# battery.net
KiCad netlist of a schematic drawn in Altium Designer
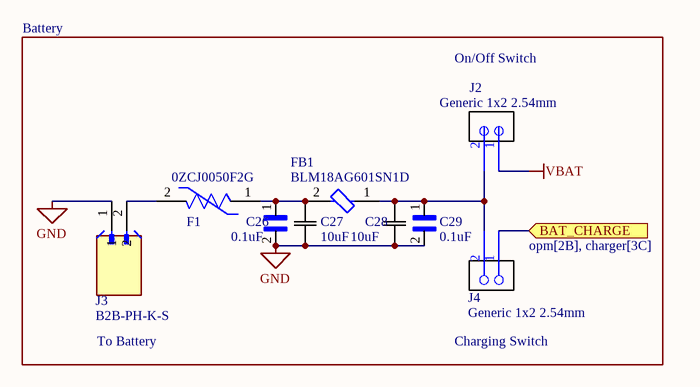
[diagram p0: battery.SchDoc]

(export (version "E")
  (design (tool "Eeschema 10.0.6"))
  (components
    (comp (ref "C26")
      (value "0.1uF")
      (footprint "CC0603JRX7R8BB104")
      (description "25V 100nF X7R ±5% 0603 Multilayer Ceramic Capacitors MLCC - SMD/SMT ROHS")
      (fields
        (field (name "MANUFACTURER") "Yageo Group")
        (field (name "MANUFACTURER PART NUMBER") "CC0603JRX7R8BB104")
      )
      (libsource (lib "opm_lib") (part "CC0603JRX7R8BB104"))
    )
    (comp (ref "C27")
      (value "10uF")
      (footprint "CC0805KKX7R7BB106")
      (description "16V 10uF X7R ±10% 0805 Multilayer Ceramic Capacitors MLCC - SMD/SMT ROHS")
      (fields
        (field (name "MANUFACTURER") "Yageo Group")
        (field (name "MANUFACTURER PART NUMBER") "CC0805KKX7R7BB106")
      )
      (libsource (lib "opm_lib") (part "CC0805KKX7R7BB106"))
    )
    (comp (ref "C28")
      (value "10uF")
      (footprint "CC0805KKX7R7BB106")
      (description "16V 10uF X7R ±10% 0805 Multilayer Ceramic Capacitors MLCC - SMD/SMT ROHS")
      (fields
        (field (name "MANUFACTURER") "Yageo Group")
        (field (name "MANUFACTURER PART NUMBER") "CC0805KKX7R7BB106")
      )
      (libsource (lib "opm_lib") (part "CC0805KKX7R7BB106"))
    )
    (comp (ref "C29")
      (value "0.1uF")
      (footprint "CC0603JRX7R8BB104")
      (description "25V 100nF X7R ±5% 0603 Multilayer Ceramic Capacitors MLCC - SMD/SMT ROHS")
      (fields
        (field (name "MANUFACTURER") "Yageo Group")
        (field (name "MANUFACTURER PART NUMBER") "CC0603JRX7R8BB104")
      )
      (libsource (lib "opm_lib") (part "CC0603JRX7R8BB104"))
    )
    (comp (ref "F1")
      (value "0ZCJ0050F2G")
      (footprint "0ZCJ0050FF2G")
      (description "Resettable Fuse, PPTC, 1206 (3216 Metric), 0ZCJ Series, 8 VDC, 500 mA, 1 A, 0.1 s")
      (fields
        (field (name "MANUFACTURER") "Bel Fuse")
        (field (name "MANUFACTURER PART NUMBER") "0ZCJ0050FF2G")
      )
      (libsource (lib "opm_lib") (part "0ZCJ0050FF2G"))
    )
    (comp (ref "FB1")
      (value "BLM18AG601SN1D")
      (footprint "BLM18AG601SN1D")
      (description "Ferrite Beads Multi-Layer 600Ohm 25% 100MHz 500mA 380mOhm DCR 0603 Automotive Paper T/R")
      (fields (field (name "MANUFACTURER") "Murata") (field (name "TOLERANCE") "25%"))
      (libsource (lib "opm_lib") (part "BLM18AG601SN1D"))
    )
    (comp (ref "J2")
      (value "Generic 1x2 2.54mm")
      (footprint "GENERIC 1X2 2.54mm")
      (libsource (lib "opm_lib") (part "Generic 1x2 2.54mm"))
    )
    (comp (ref "J3")
      (value "B2B-PH-K-S")
      (footprint "JST_B2B-PH-K-S")
      (description "CONN HEADER VERT 2POS 2MM / 2.0mm pitch/Disconnectable Crimp style connectors")
      (fields (field (name "MANUFACTURER") "JST"))
      (libsource (lib "opm_lib") (part "B2B-PH-K-S"))
    )
    (comp (ref "J4")
      (value "Generic 1x2 2.54mm")
      (footprint "GENERIC 1X2 2.54mm")
      (libsource (lib "opm_lib") (part "Generic 1x2 2.54mm"))
    )
  )
  (nets
    (net (code "1") (name "/BAT_CHARGE") (class "Default")
      (node (ref "J4") (pin "1") (pinfunction "1_1") (pintype "passive"))
    )
    (net (code "2") (name "GND") (class "Default")
      (node (ref "C26") (pin "2") (pinfunction "2_2") (pintype "passive"))
      (node (ref "C27") (pin "1") (pinfunction "1_1") (pintype "passive"))
      (node (ref "C28") (pin "1") (pinfunction "1_1") (pintype "passive"))
      (node (ref "C29") (pin "2") (pinfunction "2_2") (pintype "passive"))
      (node (ref "J3") (pin "1") (pinfunction "1_1") (pintype "passive"))
    )
    (net (code "3") (name "Net-(C26-Pad1)") (class "Default")
      (node (ref "C26") (pin "1") (pinfunction "1_1") (pintype "passive"))
      (node (ref "C27") (pin "2") (pinfunction "2_2") (pintype "passive"))
      (node (ref "F1") (pin "1") (pinfunction "1_1") (pintype "passive"))
      (node (ref "FB1") (pin "2") (pinfunction "2_2") (pintype "passive"))
    )
    (net (code "4") (name "Net-(C28-Pad2)") (class "Default")
      (node (ref "C28") (pin "2") (pinfunction "2_2") (pintype "passive"))
      (node (ref "C29") (pin "1") (pinfunction "1_1") (pintype "passive"))
      (node (ref "FB1") (pin "1") (pinfunction "1_1") (pintype "passive"))
      (node (ref "J2") (pin "2") (pinfunction "2_2") (pintype "passive"))
      (node (ref "J4") (pin "2") (pinfunction "2_2") (pintype "passive"))
    )
    (net (code "5") (name "Net-(F1-Pad2)") (class "Default")
      (node (ref "F1") (pin "2") (pinfunction "2_2") (pintype "passive"))
      (node (ref "J3") (pin "2") (pinfunction "2_2") (pintype "passive"))
    )
    (net (code "6") (name "VBAT") (class "Default")
      (node (ref "J2") (pin "1") (pinfunction "1_1") (pintype "passive"))
    )
  )
)
